# cell.net
KiCad netlist of a schematic drawn in EAGLE
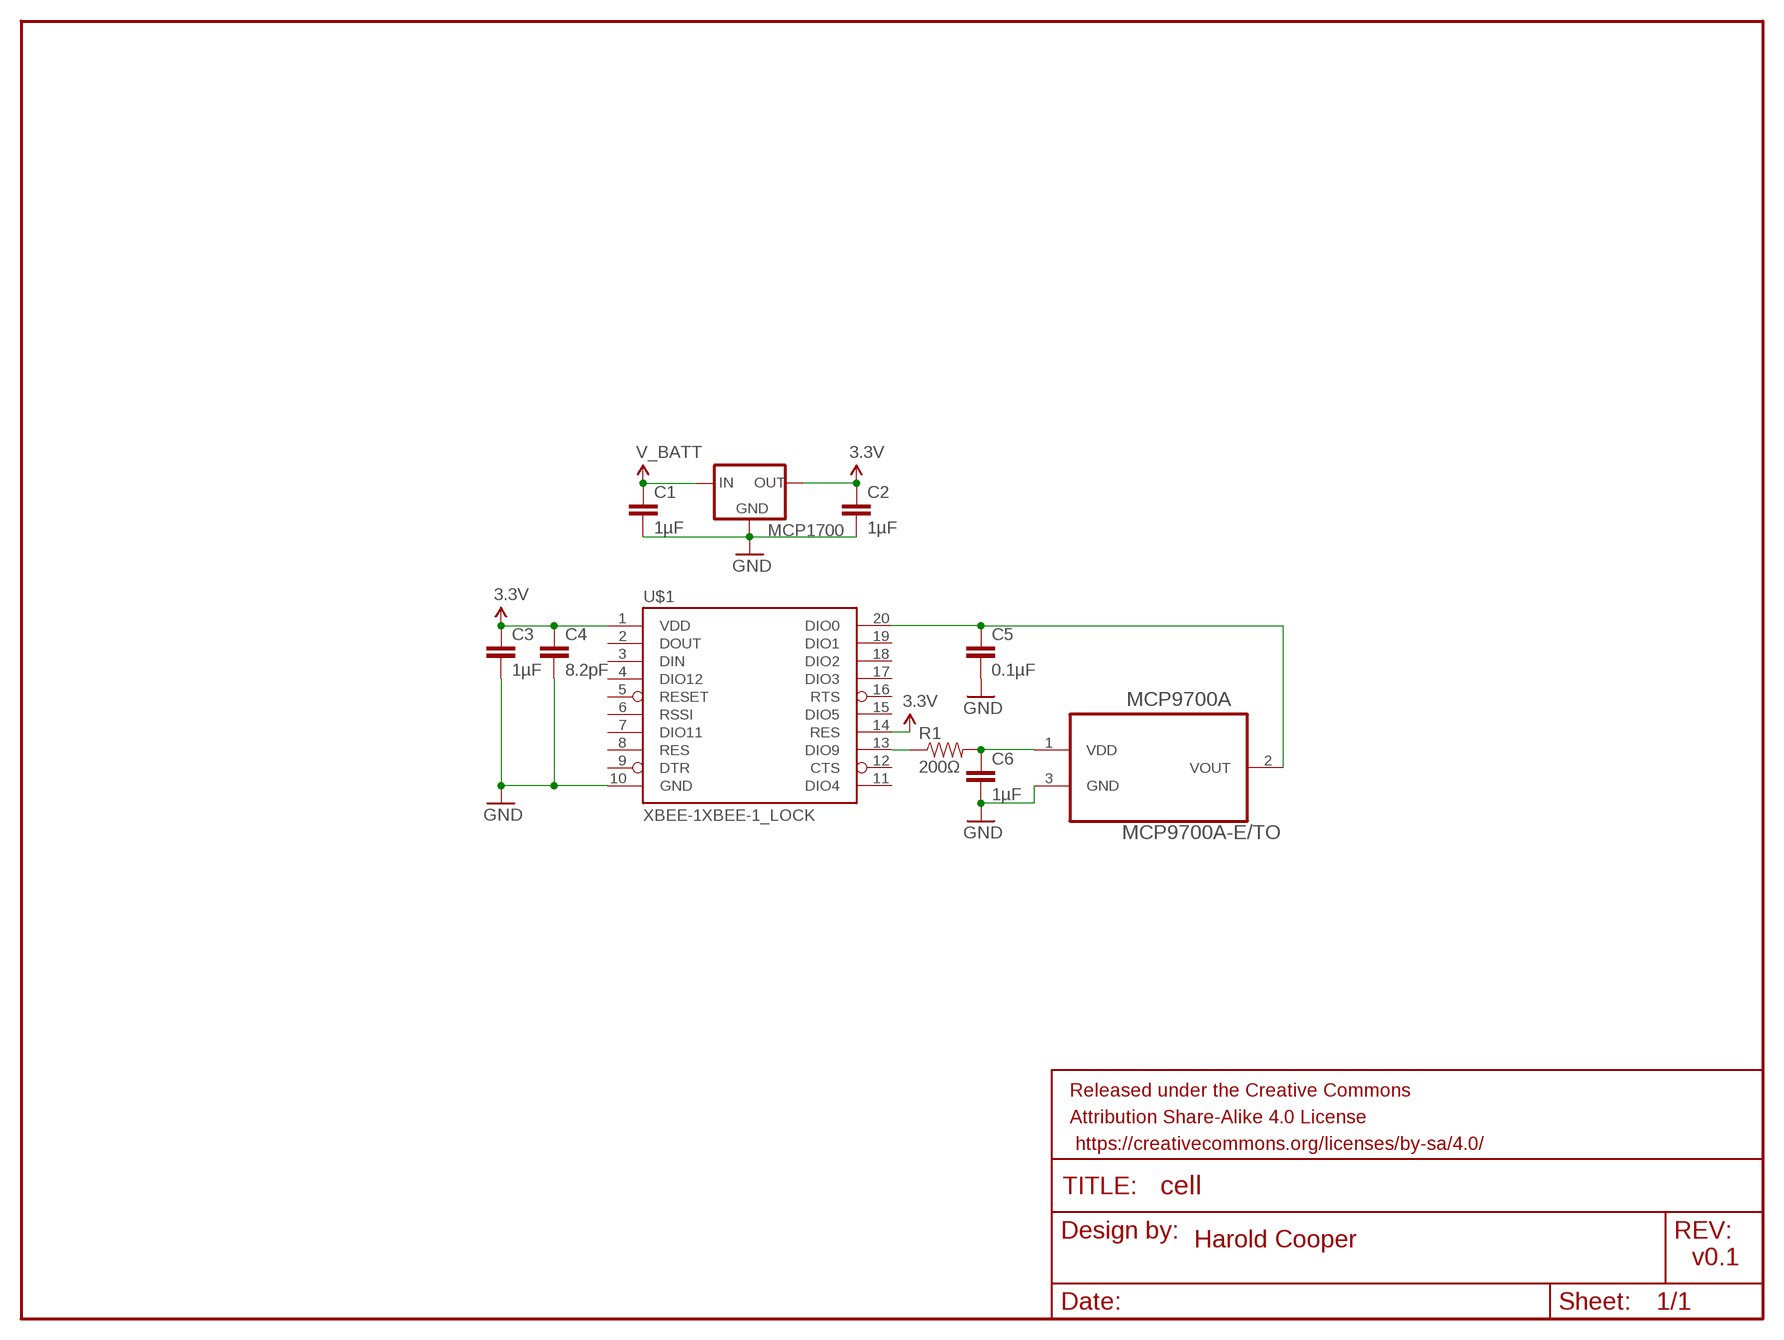
[diagram p0: schematic, sheet 1]

(export (version "E")
  (design (tool "Eeschema 10.0.6"))
  (components
    (comp (ref "C1")
      (value "1µF")
      (footprint "eagle-import:0805")
      (libsource (lib "eagle-import") (part "CAP0805"))
    )
    (comp (ref "C2")
      (value "1µF")
      (footprint "eagle-import:0805")
      (libsource (lib "eagle-import") (part "CAP0805"))
    )
    (comp (ref "C3")
      (value "1µF")
      (footprint "eagle-import:0805")
      (libsource (lib "eagle-import") (part "CAP0805"))
    )
    (comp (ref "C4")
      (value "8.2pF")
      (footprint "eagle-import:0805")
      (libsource (lib "eagle-import") (part "CAP0805"))
    )
    (comp (ref "C5")
      (value "0.1µF")
      (footprint "eagle-import:0805")
      (libsource (lib "eagle-import") (part "CAP0805"))
    )
    (comp (ref "C6")
      (value "1µF")
      (footprint "eagle-import:0805")
      (libsource (lib "eagle-import") (part "CAP0805"))
    )
    (comp (ref "FRAME1")
      (value "FRAME-LETTER")
      (footprint "eagle-import:CREATIVE_COMMONS")
      (libsource (lib "eagle-import") (part "FRAME-LETTER"))
    )
    (comp (ref "MCP1700")
      (value "MCP1700INLINE")
      (footprint "eagle-import:TO92-INLINE")
      (libsource (lib "eagle-import") (part "MCP1700INLINE"))
    )
    (comp (ref "MCP9700A")
      (value "MCP9700A-E/TO")
      (footprint "eagle-import:TO127P254X533-3")
      (libsource (lib "eagle-import") (part "MCP9700A-E/TO"))
    )
    (comp (ref "R1")
      (value "200Ω")
      (footprint "eagle-import:0805")
      (libsource (lib "eagle-import") (part "RESISTOR0805-RES"))
    )
    (comp (ref "U$1")
      (value "XBEE-1XBEE-1_LOCK")
      (footprint "eagle-import:XBEE-1_LOCK")
      (libsource (lib "eagle-import") (part "XBEE-1XBEE-1_LOCK"))
    )
  )
  (nets
    (net (code "1") (name "3.3V") (class "Default")
      (node (ref "C2") (pin "1") (pinfunction "1_1") (pintype "passive"))
      (node (ref "C3") (pin "1") (pinfunction "1_1") (pintype "passive"))
      (node (ref "C4") (pin "1") (pinfunction "1_1") (pintype "passive"))
      (node (ref "MCP1700") (pin "3") (pinfunction "OUT_3") (pintype "passive"))
      (node (ref "U$1") (pin "1") (pinfunction "VDD_1") (pintype "power_in"))
      (node (ref "U$1") (pin "14") (pinfunction "RES_14") (pintype "bidirectional"))
    )
    (net (code "2") (name "GND") (class "Default")
      (node (ref "C1") (pin "2") (pinfunction "2_2") (pintype "passive"))
      (node (ref "C2") (pin "2") (pinfunction "2_2") (pintype "passive"))
      (node (ref "C3") (pin "2") (pinfunction "2_2") (pintype "passive"))
      (node (ref "C4") (pin "2") (pinfunction "2_2") (pintype "passive"))
      (node (ref "C5") (pin "2") (pinfunction "2_2") (pintype "passive"))
      (node (ref "C6") (pin "2") (pinfunction "2_2") (pintype "passive"))
      (node (ref "MCP1700") (pin "1") (pinfunction "GND_1") (pintype "input"))
      (node (ref "MCP9700A") (pin "3") (pinfunction "GND_3") (pintype "passive"))
      (node (ref "U$1") (pin "10") (pinfunction "GND_10") (pintype "power_in"))
    )
    (net (code "3") (name "Net-(MCP9700A-VDD)") (class "Default")
      (node (ref "C6") (pin "1") (pinfunction "1_1") (pintype "passive"))
      (node (ref "MCP9700A") (pin "1") (pinfunction "VDD_1") (pintype "power_in"))
      (node (ref "R1") (pin "2") (pinfunction "2_2") (pintype "passive"))
    )
    (net (code "4") (name "Net-(MCP9700A-VOUT)") (class "Default")
      (node (ref "C5") (pin "1") (pinfunction "1_1") (pintype "passive"))
      (node (ref "MCP9700A") (pin "2") (pinfunction "VOUT_2") (pintype "output"))
      (node (ref "U$1") (pin "20") (pinfunction "DIO0_20") (pintype "bidirectional"))
    )
    (net (code "5") (name "Net-(U$1-DIO9)") (class "Default")
      (node (ref "R1") (pin "1") (pinfunction "1_1") (pintype "passive"))
      (node (ref "U$1") (pin "13") (pinfunction "DIO9_13") (pintype "bidirectional"))
    )
    (net (code "6") (name "V_BATT") (class "Default")
      (node (ref "C1") (pin "1") (pinfunction "1_1") (pintype "passive"))
      (node (ref "MCP1700") (pin "2") (pinfunction "IN_2") (pintype "input"))
    )
    (net (code "7") (name "unconnected-(U$1-CTS-Pad12)") (class "Default")
      (node (ref "U$1") (pin "12") (pinfunction "CTS_12") (pintype "output"))
    )
    (net (code "8") (name "unconnected-(U$1-DIN-Pad3)") (class "Default")
      (node (ref "U$1") (pin "3") (pinfunction "DIN_3") (pintype "input"))
    )
    (net (code "9") (name "unconnected-(U$1-DIO1-Pad19)") (class "Default")
      (node (ref "U$1") (pin "19") (pinfunction "DIO1_19") (pintype "bidirectional"))
    )
    (net (code "10") (name "unconnected-(U$1-DIO2-Pad18)") (class "Default")
      (node (ref "U$1") (pin "18") (pinfunction "DIO2_18") (pintype "bidirectional"))
    )
    (net (code "11") (name "unconnected-(U$1-DIO3-Pad17)") (class "Default")
      (node (ref "U$1") (pin "17") (pinfunction "DIO3_17") (pintype "bidirectional"))
    )
    (net (code "12") (name "unconnected-(U$1-DIO4-Pad11)") (class "Default")
      (node (ref "U$1") (pin "11") (pinfunction "DIO4_11") (pintype "bidirectional"))
    )
    (net (code "13") (name "unconnected-(U$1-DIO5-Pad15)") (class "Default")
      (node (ref "U$1") (pin "15") (pinfunction "DIO5_15") (pintype "bidirectional"))
    )
    (net (code "14") (name "unconnected-(U$1-DIO11-Pad7)") (class "Default")
      (node (ref "U$1") (pin "7") (pinfunction "DIO11_7") (pintype "bidirectional"))
    )
    (net (code "15") (name "unconnected-(U$1-DIO12-Pad4)") (class "Default")
      (node (ref "U$1") (pin "4") (pinfunction "DIO12_4") (pintype "bidirectional"))
    )
    (net (code "16") (name "unconnected-(U$1-DOUT-Pad2)") (class "Default")
      (node (ref "U$1") (pin "2") (pinfunction "DOUT_2") (pintype "output"))
    )
    (net (code "17") (name "unconnected-(U$1-DTR-Pad9)") (class "Default")
      (node (ref "U$1") (pin "9") (pinfunction "DTR_9") (pintype "bidirectional"))
    )
    (net (code "18") (name "unconnected-(U$1-RES-Pad8)") (class "Default")
      (node (ref "U$1") (pin "8") (pinfunction "RES_8") (pintype "bidirectional"))
    )
    (net (code "19") (name "unconnected-(U$1-RESET-Pad5)") (class "Default")
      (node (ref "U$1") (pin "5") (pinfunction "RESET_5") (pintype "input"))
    )
    (net (code "20") (name "unconnected-(U$1-RSSI-Pad6)") (class "Default")
      (node (ref "U$1") (pin "6") (pinfunction "RSSI_6") (pintype "bidirectional"))
    )
    (net (code "21") (name "unconnected-(U$1-RTS-Pad16)") (class "Default")
      (node (ref "U$1") (pin "16") (pinfunction "RTS_16") (pintype "input"))
    )
  )
)
